# Battery_Block.net
KiCad netlist of a schematic drawn in EAGLE
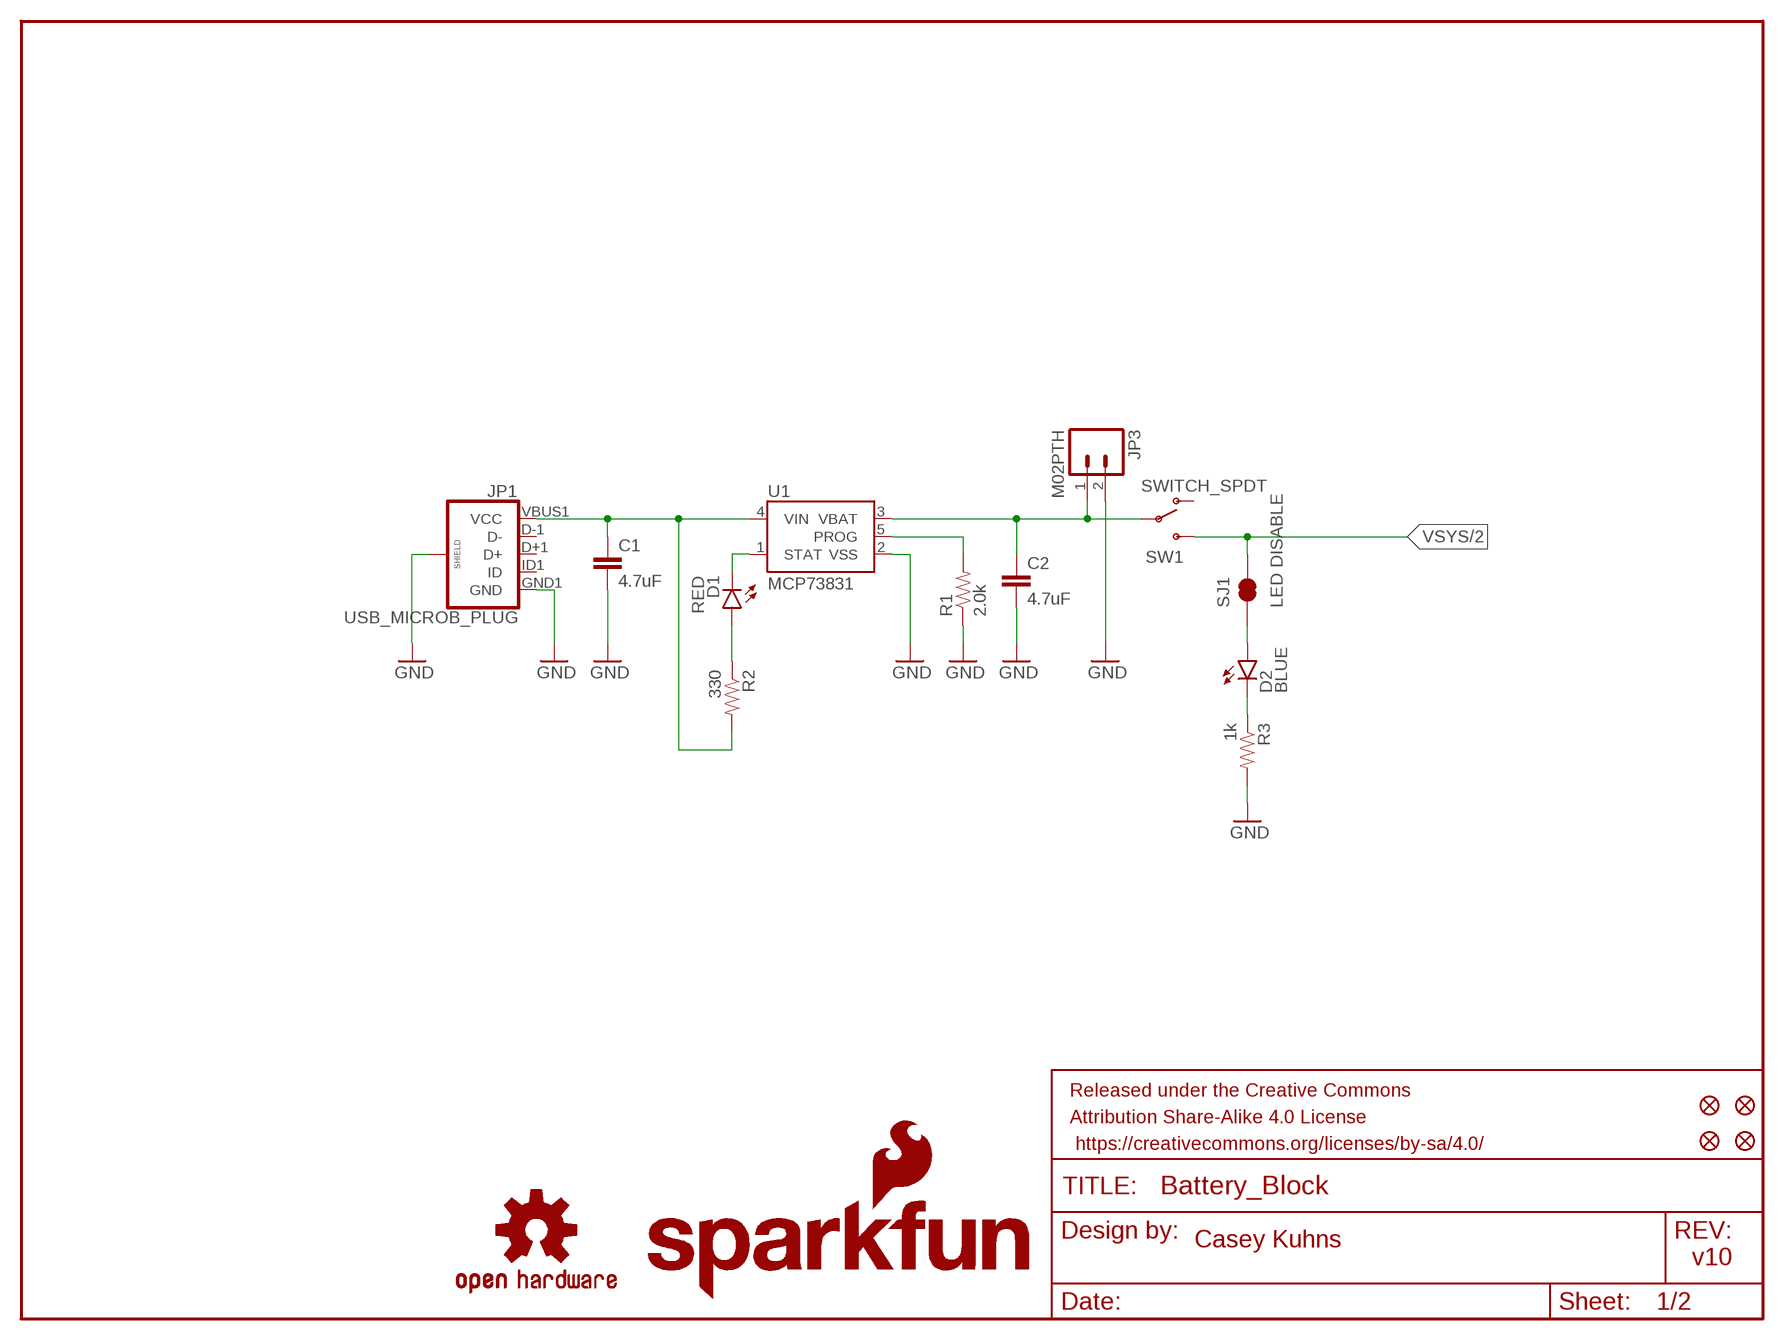
[diagram p0: schematic, sheet 1]
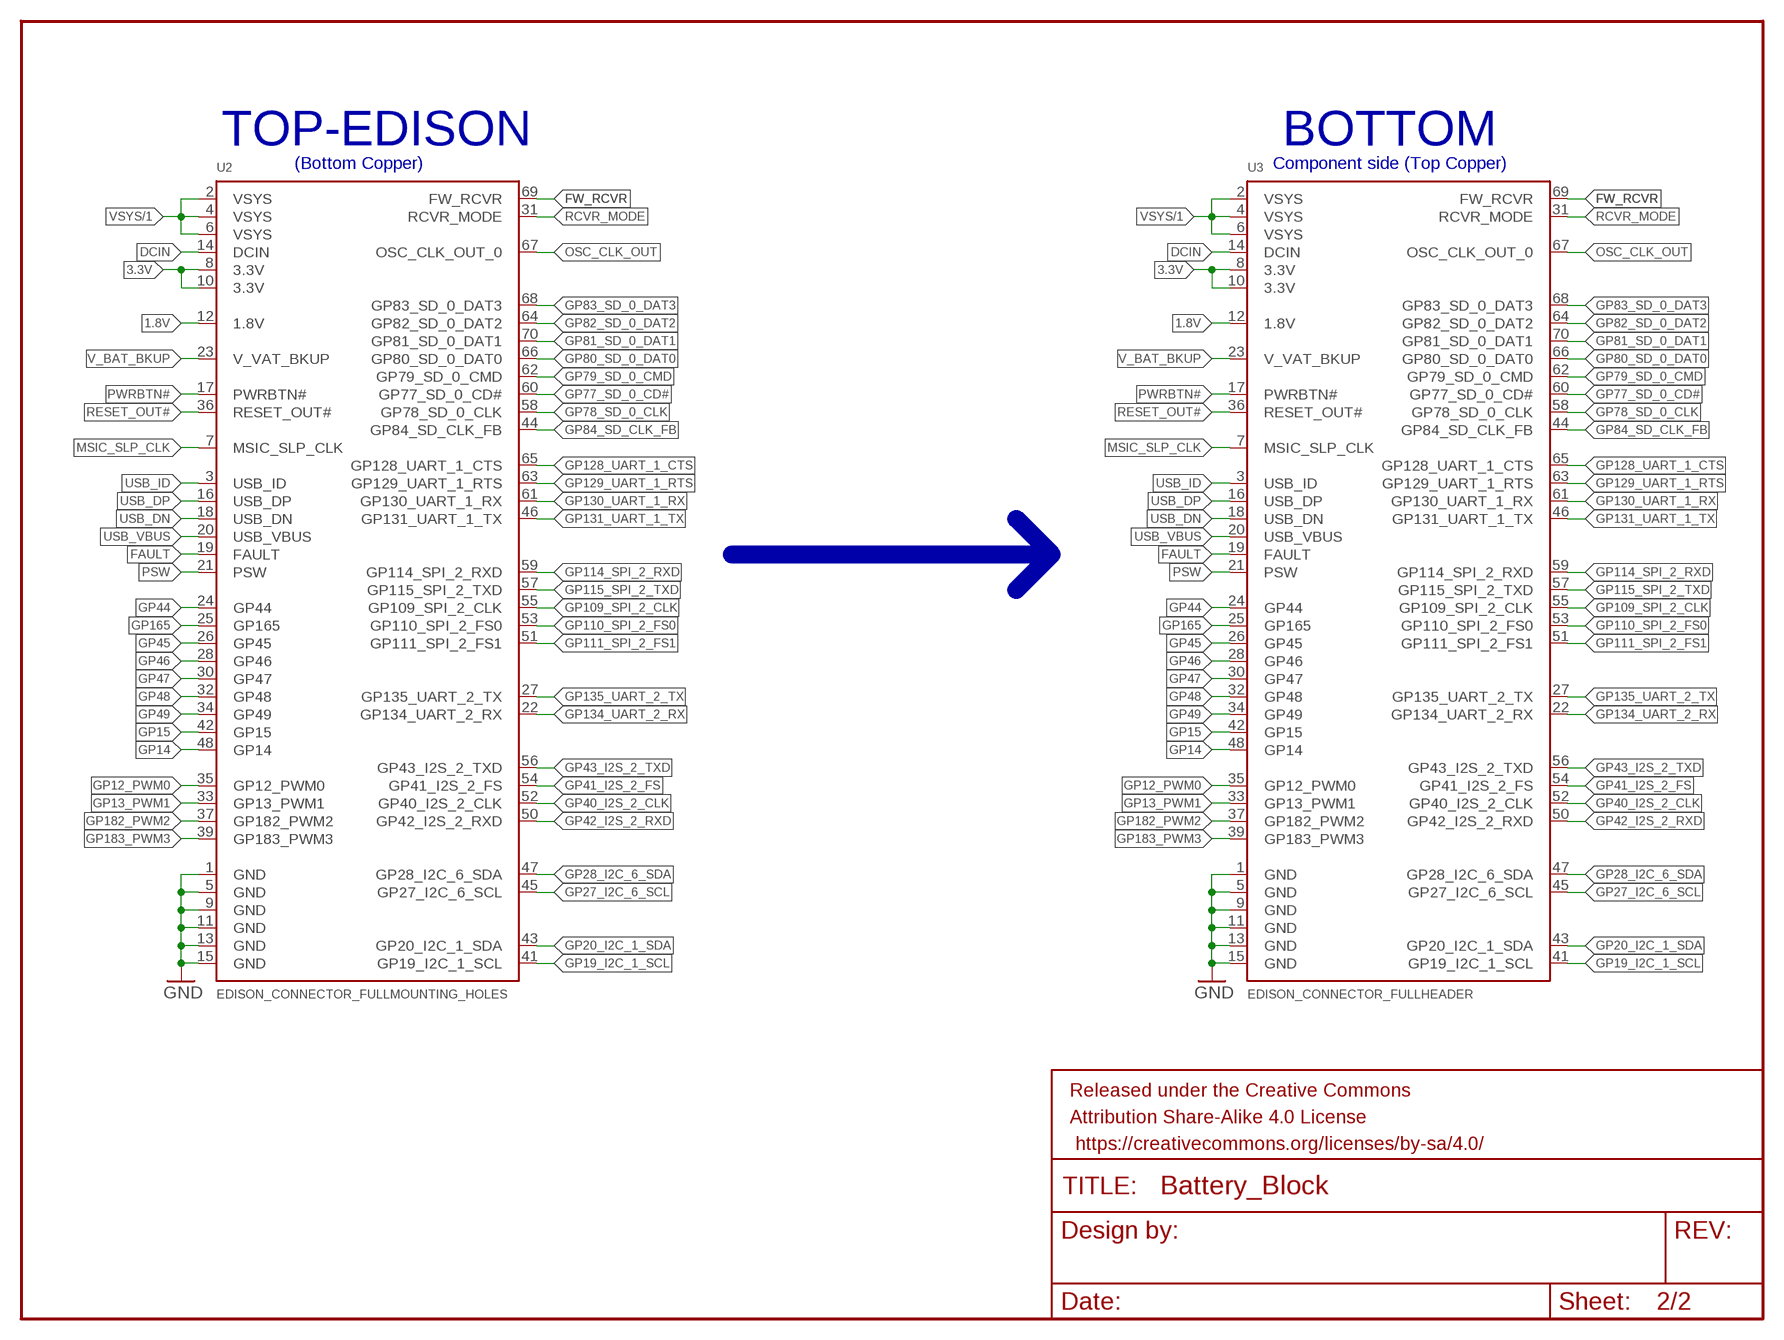
[diagram p1: schematic, sheet 2]

(export (version "E")
  (design (tool "Eeschema 10.0.6"))
  (components
    (comp (ref "FRAME2")
      (value "FRAME-LETTER")
      (footprint "eagle-import:CREATIVE_COMMONS")
      (libsource (lib "eagle-import") (part "FRAME-LETTER"))
    )
    (comp (ref "U2")
      (value "EDISON_CONNECTOR_FULLMOUNTING_HOLES")
      (footprint "eagle-import:EDISON_DAUGHTER")
      (libsource (lib "eagle-import") (part "EDISON_CONNECTOR_FULLMOUNTING_HOLES"))
    )
    (comp (ref "U3")
      (value "EDISON_CONNECTOR_FULLHEADER")
      (footprint "eagle-import:DF40C-70DP-0.4(51)")
      (libsource (lib "eagle-import") (part "EDISON_CONNECTOR_FULLHEADER"))
    )
    (comp (ref "C1")
      (value "4.7uF")
      (footprint "eagle-import:0603-CAP")
      (libsource (lib "eagle-import") (part "4.7UF-6.3V-10%(0603)0603"))
    )
    (comp (ref "C2")
      (value "4.7uF")
      (footprint "eagle-import:0603-CAP")
      (libsource (lib "eagle-import") (part "4.7UF-6.3V-10%(0603)0603"))
    )
    (comp (ref "D1")
      (value "RED")
      (footprint "eagle-import:LED-0603")
      (libsource (lib "eagle-import") (part "LED-RED0603"))
    )
    (comp (ref "D2")
      (value "BLUE")
      (footprint "eagle-import:LED-0603")
      (libsource (lib "eagle-import") (part "LED-BLUE0603"))
    )
    (comp (ref "FID1")
      (value "FIDUCIAL1X2")
      (footprint "eagle-import:FIDUCIAL-1X2")
      (libsource (lib "eagle-import") (part "FIDUCIAL1X2"))
    )
    (comp (ref "FID2")
      (value "FIDUCIAL1X2")
      (footprint "eagle-import:FIDUCIAL-1X2")
      (libsource (lib "eagle-import") (part "FIDUCIAL1X2"))
    )
    (comp (ref "FID3")
      (value "FIDUCIAL1X2")
      (footprint "eagle-import:FIDUCIAL-1X2")
      (libsource (lib "eagle-import") (part "FIDUCIAL1X2"))
    )
    (comp (ref "FID4")
      (value "FIDUCIAL1X2")
      (footprint "eagle-import:FIDUCIAL-1X2")
      (libsource (lib "eagle-import") (part "FIDUCIAL1X2"))
    )
    (comp (ref "FRAME1")
      (value "FRAME-LETTER")
      (footprint "eagle-import:CREATIVE_COMMONS")
      (libsource (lib "eagle-import") (part "FRAME-LETTER"))
    )
    (comp (ref "JP1")
      (value "USB_MICROB_PLUG")
      (footprint "eagle-import:USB-B-MICRO-SMD_V03")
      (libsource (lib "eagle-import") (part "USB_MICROB_PLUGCONN-11752"))
    )
    (comp (ref "JP3")
      (value "M02PTH")
      (footprint "eagle-import:1X02")
      (libsource (lib "eagle-import") (part "M02PTH"))
    )
    (comp (ref "LOGO1")
      (value "OSHW-LOGOS")
      (footprint "eagle-import:OSHW-LOGO-S")
      (libsource (lib "eagle-import") (part "OSHW-LOGOS"))
    )
    (comp (ref "LOGO4")
      (value "SFE_LOGO_NAME_FLAME.1_INCH")
      (footprint "eagle-import:SFE_LOGO_NAME_FLAME_.1")
      (libsource (lib "eagle-import") (part "SFE_LOGO_NAME_FLAME.1_INCH"))
    )
    (comp (ref "R1")
      (value "2.0k")
      (footprint "eagle-import:0603-RES")
      (libsource (lib "eagle-import") (part "2.0KOHM1/10W5%(0603)"))
    )
    (comp (ref "R2")
      (value "330")
      (footprint "eagle-import:0603-RES")
      (libsource (lib "eagle-import") (part "330OHM1/10W1%(0603)"))
    )
    (comp (ref "R3")
      (value "1k")
      (footprint "eagle-import:0603-RES")
      (libsource (lib "eagle-import") (part "1KOHM1/10W1%(0603)"))
    )
    (comp (ref "SJ1")
      (value "LED DISABLE")
      (footprint "eagle-import:PAD-JUMPER-2-NC_BY_TRACE_YES_SILK")
      (libsource (lib "eagle-import") (part "JUMPER-PAD-2-NC_BY_TRACE"))
    )
    (comp (ref "SW1")
      (value "SWITCH_SPDT")
      (footprint "eagle-import:KPS-1290")
      (libsource (lib "eagle-import") (part "SWITCH_SPDT"))
    )
    (comp (ref "U1")
      (value "MCP73831")
      (footprint "eagle-import:SOT23-5")
      (libsource (lib "eagle-import") (part "MCP73831"))
    )
  )
  (nets
    (net (code "1") (name "1.8V") (class "Default")
      (node (ref "U2") (pin "12") (pinfunction "1.8V_12") (pintype "bidirectional"))
      (node (ref "U3") (pin "12") (pinfunction "1.8V_12") (pintype "bidirectional"))
    )
    (net (code "2") (name "3.3V") (class "Default")
      (node (ref "U2") (pin "10") (pinfunction "3.3V_10") (pintype "bidirectional"))
      (node (ref "U2") (pin "8") (pinfunction "3.3V_8") (pintype "bidirectional"))
      (node (ref "U3") (pin "10") (pinfunction "3.3V_10") (pintype "bidirectional"))
      (node (ref "U3") (pin "8") (pinfunction "3.3V_8") (pintype "bidirectional"))
    )
    (net (code "3") (name "DCIN") (class "Default")
      (node (ref "U2") (pin "14") (pinfunction "DCIN_14") (pintype "bidirectional"))
      (node (ref "U3") (pin "14") (pinfunction "DCIN_14") (pintype "bidirectional"))
    )
    (net (code "4") (name "FAULT") (class "Default")
      (node (ref "U2") (pin "19") (pinfunction "FAULT_19") (pintype "bidirectional"))
      (node (ref "U3") (pin "19") (pinfunction "FAULT_19") (pintype "bidirectional"))
    )
    (net (code "5") (name "FW_RCVR") (class "Default")
      (node (ref "U2") (pin "69") (pinfunction "FW_RCVR_69") (pintype "bidirectional"))
      (node (ref "U3") (pin "69") (pinfunction "FW_RCVR_69") (pintype "bidirectional"))
    )
    (net (code "6") (name "GND") (class "Default")
      (node (ref "C1") (pin "2") (pinfunction "2_2") (pintype "passive"))
      (node (ref "C2") (pin "2") (pinfunction "2_2") (pintype "passive"))
      (node (ref "JP1") (pin "GND1") (pinfunction "GND_GND1") (pintype "bidirectional"))
      (node (ref "JP1") (pin "SHIELD1") (pinfunction "SHIELD_SHIELD1") (pintype "bidirectional"))
      (node (ref "JP1") (pin "SHIELD2") (pinfunction "SHIELD_SHIELD2") (pintype "bidirectional"))
      (node (ref "JP1") (pin "SHIELD3") (pinfunction "SHIELD_SHIELD3") (pintype "bidirectional"))
      (node (ref "JP3") (pin "2") (pinfunction "2_2") (pintype "passive"))
      (node (ref "R1") (pin "1") (pinfunction "1_1") (pintype "passive"))
      (node (ref "R3") (pin "2") (pinfunction "2_2") (pintype "passive"))
      (node (ref "U1") (pin "2") (pinfunction "VSS_2") (pintype "power_in"))
      (node (ref "U2") (pin "1") (pinfunction "GND_1") (pintype "bidirectional"))
      (node (ref "U2") (pin "11") (pinfunction "GND_11") (pintype "bidirectional"))
      (node (ref "U2") (pin "13") (pinfunction "GND_13") (pintype "bidirectional"))
      (node (ref "U2") (pin "15") (pinfunction "GND_15") (pintype "bidirectional"))
      (node (ref "U2") (pin "5") (pinfunction "GND_5") (pintype "bidirectional"))
      (node (ref "U2") (pin "9") (pinfunction "GND_9") (pintype "bidirectional"))
      (node (ref "U3") (pin "1") (pinfunction "GND_1") (pintype "bidirectional"))
      (node (ref "U3") (pin "11") (pinfunction "GND_11") (pintype "bidirectional"))
      (node (ref "U3") (pin "13") (pinfunction "GND_13") (pintype "bidirectional"))
      (node (ref "U3") (pin "15") (pinfunction "GND_15") (pintype "bidirectional"))
      (node (ref "U3") (pin "5") (pinfunction "GND_5") (pintype "bidirectional"))
      (node (ref "U3") (pin "9") (pinfunction "GND_9") (pintype "bidirectional"))
    )
    (net (code "7") (name "GP12_PWM0") (class "Default")
      (node (ref "U2") (pin "35") (pinfunction "GP12_PWM0_35") (pintype "bidirectional"))
      (node (ref "U3") (pin "35") (pinfunction "GP12_PWM0_35") (pintype "bidirectional"))
    )
    (net (code "8") (name "GP13_PWM1") (class "Default")
      (node (ref "U2") (pin "33") (pinfunction "GP13_PWM1_33") (pintype "bidirectional"))
      (node (ref "U3") (pin "33") (pinfunction "GP13_PWM1_33") (pintype "bidirectional"))
    )
    (net (code "9") (name "GP14") (class "Default")
      (node (ref "U2") (pin "48") (pinfunction "GP14_48") (pintype "bidirectional"))
      (node (ref "U3") (pin "48") (pinfunction "GP14_48") (pintype "bidirectional"))
    )
    (net (code "10") (name "GP15") (class "Default")
      (node (ref "U2") (pin "42") (pinfunction "GP15_42") (pintype "bidirectional"))
      (node (ref "U3") (pin "42") (pinfunction "GP15_42") (pintype "bidirectional"))
    )
    (net (code "11") (name "GP19_I2C_1_SCL") (class "Default")
      (node (ref "U2") (pin "41") (pinfunction "GP19_I2C_1_SCL_41") (pintype "bidirectional"))
      (node (ref "U3") (pin "41") (pinfunction "GP19_I2C_1_SCL_41") (pintype "bidirectional"))
    )
    (net (code "12") (name "GP20_I2C_1_SDA") (class "Default")
      (node (ref "U2") (pin "43") (pinfunction "GP20_I2C_1_SDA_43") (pintype "bidirectional"))
      (node (ref "U3") (pin "43") (pinfunction "GP20_I2C_1_SDA_43") (pintype "bidirectional"))
    )
    (net (code "13") (name "GP27_I2C_6_SCL") (class "Default")
      (node (ref "U2") (pin "45") (pinfunction "GP27_I2C_6_SCL_45") (pintype "bidirectional"))
      (node (ref "U3") (pin "45") (pinfunction "GP27_I2C_6_SCL_45") (pintype "bidirectional"))
    )
    (net (code "14") (name "GP28_I2C_6_SDA") (class "Default")
      (node (ref "U2") (pin "47") (pinfunction "GP28_I2C_6_SDA_47") (pintype "bidirectional"))
      (node (ref "U3") (pin "47") (pinfunction "GP28_I2C_6_SDA_47") (pintype "bidirectional"))
    )
    (net (code "15") (name "GP40_I2S_2_CLK") (class "Default")
      (node (ref "U2") (pin "52") (pinfunction "GP40_I2S_2_CLK_52") (pintype "bidirectional"))
      (node (ref "U3") (pin "52") (pinfunction "GP40_I2S_2_CLK_52") (pintype "bidirectional"))
    )
    (net (code "16") (name "GP41_I2S_2_FS") (class "Default")
      (node (ref "U2") (pin "54") (pinfunction "GP41_I2S_2_FS_54") (pintype "bidirectional"))
      (node (ref "U3") (pin "54") (pinfunction "GP41_I2S_2_FS_54") (pintype "bidirectional"))
    )
    (net (code "17") (name "GP42_I2S_2_RXD") (class "Default")
      (node (ref "U2") (pin "50") (pinfunction "GP42_I2S_2_RXD_50") (pintype "bidirectional"))
      (node (ref "U3") (pin "50") (pinfunction "GP42_I2S_2_RXD_50") (pintype "bidirectional"))
    )
    (net (code "18") (name "GP43_I2S_2_TXD") (class "Default")
      (node (ref "U2") (pin "56") (pinfunction "GP43_I2S_2_TXD_56") (pintype "bidirectional"))
      (node (ref "U3") (pin "56") (pinfunction "GP43_I2S_2_TXD_56") (pintype "bidirectional"))
    )
    (net (code "19") (name "GP44") (class "Default")
      (node (ref "U2") (pin "24") (pinfunction "GP44_24") (pintype "bidirectional"))
      (node (ref "U3") (pin "24") (pinfunction "GP44_24") (pintype "bidirectional"))
    )
    (net (code "20") (name "GP45") (class "Default")
      (node (ref "U2") (pin "26") (pinfunction "GP45_26") (pintype "bidirectional"))
      (node (ref "U3") (pin "26") (pinfunction "GP45_26") (pintype "bidirectional"))
    )
    (net (code "21") (name "GP46") (class "Default")
      (node (ref "U2") (pin "28") (pinfunction "GP46_28") (pintype "bidirectional"))
      (node (ref "U3") (pin "28") (pinfunction "GP46_28") (pintype "bidirectional"))
    )
    (net (code "22") (name "GP47") (class "Default")
      (node (ref "U2") (pin "30") (pinfunction "GP47_30") (pintype "bidirectional"))
      (node (ref "U3") (pin "30") (pinfunction "GP47_30") (pintype "bidirectional"))
    )
    (net (code "23") (name "GP48") (class "Default")
      (node (ref "U2") (pin "32") (pinfunction "GP48_32") (pintype "bidirectional"))
      (node (ref "U3") (pin "32") (pinfunction "GP48_32") (pintype "bidirectional"))
    )
    (net (code "24") (name "GP49") (class "Default")
      (node (ref "U2") (pin "34") (pinfunction "GP49_34") (pintype "bidirectional"))
      (node (ref "U3") (pin "34") (pinfunction "GP49_34") (pintype "bidirectional"))
    )
    (net (code "25") (name "GP77_SD_0_CD#") (class "Default")
      (node (ref "U2") (pin "60") (pinfunction "GP77_SD_0_CD#_60") (pintype "bidirectional"))
      (node (ref "U3") (pin "60") (pinfunction "GP77_SD_0_CD#_60") (pintype "bidirectional"))
    )
    (net (code "26") (name "GP78_SD_0_CLK") (class "Default")
      (node (ref "U2") (pin "58") (pinfunction "GP78_SD_0_CLK_58") (pintype "bidirectional"))
      (node (ref "U3") (pin "58") (pinfunction "GP78_SD_0_CLK_58") (pintype "bidirectional"))
    )
    (net (code "27") (name "GP79_SD_0_CMD") (class "Default")
      (node (ref "U2") (pin "62") (pinfunction "GP79_SD_0_CMD_62") (pintype "bidirectional"))
      (node (ref "U3") (pin "62") (pinfunction "GP79_SD_0_CMD_62") (pintype "bidirectional"))
    )
    (net (code "28") (name "GP80_SD_0_DAT0") (class "Default")
      (node (ref "U2") (pin "66") (pinfunction "GP80_SD_0_DAT0_66") (pintype "bidirectional"))
      (node (ref "U3") (pin "66") (pinfunction "GP80_SD_0_DAT0_66") (pintype "bidirectional"))
    )
    (net (code "29") (name "GP81_SD_0_DAT1") (class "Default")
      (node (ref "U2") (pin "70") (pinfunction "GP81_SD_0_DAT1_70") (pintype "bidirectional"))
      (node (ref "U3") (pin "70") (pinfunction "GP81_SD_0_DAT1_70") (pintype "bidirectional"))
    )
    (net (code "30") (name "GP82_SD_0_DAT2") (class "Default")
      (node (ref "U2") (pin "64") (pinfunction "GP82_SD_0_DAT2_64") (pintype "bidirectional"))
      (node (ref "U3") (pin "64") (pinfunction "GP82_SD_0_DAT2_64") (pintype "bidirectional"))
    )
    (net (code "31") (name "GP83_SD_0_DAT3") (class "Default")
      (node (ref "U2") (pin "68") (pinfunction "GP83_SD_0_DAT3_68") (pintype "bidirectional"))
      (node (ref "U3") (pin "68") (pinfunction "GP83_SD_0_DAT3_68") (pintype "bidirectional"))
    )
    (net (code "32") (name "GP84_SD_CLK_FB") (class "Default")
      (node (ref "U2") (pin "44") (pinfunction "GP84_SD_CLK_FB_44") (pintype "bidirectional"))
      (node (ref "U3") (pin "44") (pinfunction "GP84_SD_CLK_FB_44") (pintype "bidirectional"))
    )
    (net (code "33") (name "GP109_SPI_2_CLK") (class "Default")
      (node (ref "U2") (pin "55") (pinfunction "GP109_SPI_2_CLK_55") (pintype "bidirectional"))
      (node (ref "U3") (pin "55") (pinfunction "GP109_SPI_2_CLK_55") (pintype "bidirectional"))
    )
    (net (code "34") (name "GP110_SPI_2_FS0") (class "Default")
      (node (ref "U2") (pin "53") (pinfunction "GP110_SPI_2_FS0_53") (pintype "bidirectional"))
      (node (ref "U3") (pin "53") (pinfunction "GP110_SPI_2_FS0_53") (pintype "bidirectional"))
    )
    (net (code "35") (name "GP111_SPI_2_FS1") (class "Default")
      (node (ref "U2") (pin "51") (pinfunction "GP111_SPI_2_FS1_51") (pintype "bidirectional"))
      (node (ref "U3") (pin "51") (pinfunction "GP111_SPI_2_FS1_51") (pintype "bidirectional"))
    )
    (net (code "36") (name "GP114_SPI_2_RXD") (class "Default")
      (node (ref "U2") (pin "59") (pinfunction "GP114_SPI_2_RXD_59") (pintype "bidirectional"))
      (node (ref "U3") (pin "59") (pinfunction "GP114_SPI_2_RXD_59") (pintype "bidirectional"))
    )
    (net (code "37") (name "GP115_SPI_2_TXD") (class "Default")
      (node (ref "U2") (pin "57") (pinfunction "GP115_SPI_2_TXD_57") (pintype "bidirectional"))
      (node (ref "U3") (pin "57") (pinfunction "GP115_SPI_2_TXD_57") (pintype "bidirectional"))
    )
    (net (code "38") (name "GP128_UART_1_CTS") (class "Default")
      (node (ref "U2") (pin "65") (pinfunction "GP128_UART_1_CTS_65") (pintype "bidirectional"))
      (node (ref "U3") (pin "65") (pinfunction "GP128_UART_1_CTS_65") (pintype "bidirectional"))
    )
    (net (code "39") (name "GP129_UART_1_RTS") (class "Default")
      (node (ref "U2") (pin "63") (pinfunction "GP129_UART_1_RTS_63") (pintype "bidirectional"))
      (node (ref "U3") (pin "63") (pinfunction "GP129_UART_1_RTS_63") (pintype "bidirectional"))
    )
    (net (code "40") (name "GP130_UART_1_RX") (class "Default")
      (node (ref "U2") (pin "61") (pinfunction "GP130_UART_1_RX_61") (pintype "bidirectional"))
      (node (ref "U3") (pin "61") (pinfunction "GP130_UART_1_RX_61") (pintype "bidirectional"))
    )
    (net (code "41") (name "GP131_UART_1_TX") (class "Default")
      (node (ref "U2") (pin "46") (pinfunction "GP131_UART_1_TX_46") (pintype "bidirectional"))
      (node (ref "U3") (pin "46") (pinfunction "GP131_UART_1_TX_46") (pintype "bidirectional"))
    )
    (net (code "42") (name "GP134_UART_2_RX") (class "Default")
      (node (ref "U2") (pin "22") (pinfunction "GP134_UART_2_RX_22") (pintype "bidirectional"))
      (node (ref "U3") (pin "22") (pinfunction "GP134_UART_2_RX_22") (pintype "bidirectional"))
    )
    (net (code "43") (name "GP135_UART_2_TX") (class "Default")
      (node (ref "U2") (pin "27") (pinfunction "GP135_UART_2_TX_27") (pintype "bidirectional"))
      (node (ref "U3") (pin "27") (pinfunction "GP135_UART_2_TX_27") (pintype "bidirectional"))
    )
    (net (code "44") (name "GP165") (class "Default")
      (node (ref "U2") (pin "25") (pinfunction "GP165_25") (pintype "bidirectional"))
      (node (ref "U3") (pin "25") (pinfunction "GP165_25") (pintype "bidirectional"))
    )
    (net (code "45") (name "GP182_PWM2") (class "Default")
      (node (ref "U2") (pin "37") (pinfunction "GP182_PWM2_37") (pintype "bidirectional"))
      (node (ref "U3") (pin "37") (pinfunction "GP182_PWM2_37") (pintype "bidirectional"))
    )
    (net (code "46") (name "GP183_PWM3") (class "Default")
      (node (ref "U2") (pin "39") (pinfunction "GP183_PWM3_39") (pintype "bidirectional"))
      (node (ref "U3") (pin "39") (pinfunction "GP183_PWM3_39") (pintype "bidirectional"))
    )
    (net (code "47") (name "MSIC_SLP_CLK") (class "Default")
      (node (ref "U2") (pin "7") (pinfunction "MSIC_SLP_CLK_7") (pintype "bidirectional"))
      (node (ref "U3") (pin "7") (pinfunction "MSIC_SLP_CLK_7") (pintype "bidirectional"))
    )
    (net (code "48") (name "Net-(D1-PadA)") (class "Default")
      (node (ref "D1") (pin "A") (pinfunction "A_A") (pintype "passive"))
      (node (ref "R2") (pin "1") (pinfunction "1_1") (pintype "passive"))
    )
    (net (code "49") (name "Net-(D2-PadA)") (class "Default")
      (node (ref "D2") (pin "A") (pinfunction "A_A") (pintype "passive"))
      (node (ref "SJ1") (pin "1") (pinfunction "1_1") (pintype "passive"))
    )
    (net (code "50") (name "Net-(D2-PadC)") (class "Default")
      (node (ref "D2") (pin "C") (pinfunction "C_C") (pintype "passive"))
      (node (ref "R3") (pin "1") (pinfunction "1_1") (pintype "passive"))
    )
    (net (code "51") (name "Net-(JP1-VCC)") (class "Default")
      (node (ref "C1") (pin "1") (pinfunction "1_1") (pintype "passive"))
      (node (ref "JP1") (pin "VBUS1") (pinfunction "VCC_VBUS1") (pintype "bidirectional"))
      (node (ref "R2") (pin "2") (pinfunction "2_2") (pintype "passive"))
      (node (ref "U1") (pin "4") (pinfunction "VIN_4") (pintype "power_in"))
    )
    (net (code "52") (name "Net-(U1-PROG)") (class "Default")
      (node (ref "R1") (pin "2") (pinfunction "2_2") (pintype "passive"))
      (node (ref "U1") (pin "5") (pinfunction "PROG_5") (pintype "input"))
    )
    (net (code "53") (name "Net-(U1-STAT)") (class "Default")
      (node (ref "D1") (pin "C") (pinfunction "C_C") (pintype "passive"))
      (node (ref "U1") (pin "1") (pinfunction "STAT_1") (pintype "output"))
    )
    (net (code "54") (name "Net-(U1-VBAT)") (class "Default")
      (node (ref "C2") (pin "1") (pinfunction "1_1") (pintype "passive"))
      (node (ref "JP3") (pin "1") (pinfunction "1_1") (pintype "passive"))
      (node (ref "SW1") (pin "P") (pinfunction "P_P") (pintype "passive"))
      (node (ref "U1") (pin "3") (pinfunction "VBAT_3") (pintype "power_in"))
    )
    (net (code "55") (name "OSC_CLK_OUT") (class "Default")
      (node (ref "U2") (pin "67") (pinfunction "OSC_CLK_OUT_0_67") (pintype "bidirectional"))
      (node (ref "U3") (pin "67") (pinfunction "OSC_CLK_OUT_0_67") (pintype "bidirectional"))
    )
    (net (code "56") (name "PSW") (class "Default")
      (node (ref "U2") (pin "21") (pinfunction "PSW_21") (pintype "bidirectional"))
      (node (ref "U3") (pin "21") (pinfunction "PSW_21") (pintype "bidirectional"))
    )
    (net (code "57") (name "PWRBTN#") (class "Default")
      (node (ref "U2") (pin "17") (pinfunction "PWRBTN#_17") (pintype "bidirectional"))
      (node (ref "U3") (pin "17") (pinfunction "PWRBTN#_17") (pintype "bidirectional"))
    )
    (net (code "58") (name "RCVR_MODE") (class "Default")
      (node (ref "U2") (pin "31") (pinfunction "RCVR_MODE_31") (pintype "bidirectional"))
      (node (ref "U3") (pin "31") (pinfunction "RCVR_MODE_31") (pintype "bidirectional"))
    )
    (net (code "59") (name "RESET_OUT#") (class "Default")
      (node (ref "U2") (pin "36") (pinfunction "RESET_OUT#_36") (pintype "bidirectional"))
      (node (ref "U3") (pin "36") (pinfunction "RESET_OUT#_36") (pintype "bidirectional"))
    )
    (net (code "60") (name "USB_DN") (class "Default")
      (node (ref "U2") (pin "18") (pinfunction "USB_DN_18") (pintype "bidirectional"))
      (node (ref "U3") (pin "18") (pinfunction "USB_DN_18") (pintype "bidirectional"))
    )
    (net (code "61") (name "USB_DP") (class "Default")
      (node (ref "U2") (pin "16") (pinfunction "USB_DP_16") (pintype "bidirectional"))
      (node (ref "U3") (pin "16") (pinfunction "USB_DP_16") (pintype "bidirectional"))
    )
    (net (code "62") (name "USB_ID") (class "Default")
      (node (ref "U2") (pin "3") (pinfunction "USB_ID_3") (pintype "bidirectional"))
      (node (ref "U3") (pin "3") (pinfunction "USB_ID_3") (pintype "bidirectional"))
    )
    (net (code "63") (name "USB_VBUS") (class "Default")
      (node (ref "U2") (pin "20") (pinfunction "USB_VBUS_20") (pintype "bidirectional"))
      (node (ref "U3") (pin "20") (pinfunction "USB_VBUS_20") (pintype "bidirectional"))
    )
    (net (code "64") (name "VSYS") (class "Default")
      (node (ref "SJ1") (pin "2") (pinfunction "2_2") (pintype "passive"))
      (node (ref "SW1") (pin "S") (pinfunction "S_S") (pintype "passive"))
      (node (ref "U2") (pin "2") (pinfunction "VSYS_2") (pintype "bidirectional"))
      (node (ref "U2") (pin "4") (pinfunction "VSYS_4") (pintype "bidirectional"))
      (node (ref "U2") (pin "6") (pinfunction "VSYS_6") (pintype "bidirectional"))
      (node (ref "U3") (pin "2") (pinfunction "VSYS_2") (pintype "bidirectional"))
      (node (ref "U3") (pin "4") (pinfunction "VSYS_4") (pintype "bidirectional"))
      (node (ref "U3") (pin "6") (pinfunction "VSYS_6") (pintype "bidirectional"))
    )
    (net (code "65") (name "V_BAT_BKUP") (class "Default")
      (node (ref "U2") (pin "23") (pinfunction "V_VAT_BKUP_23") (pintype "bidirectional"))
      (node (ref "U3") (pin "23") (pinfunction "V_VAT_BKUP_23") (pintype "bidirectional"))
    )
    (net (code "66") (name "unconnected-(JP1-D+-PadD+1)") (class "Default")
      (node (ref "JP1") (pin "D+1") (pinfunction "D+_D+1") (pintype "bidirectional"))
    )
    (net (code "67") (name "unconnected-(JP1-D--PadD-1)") (class "Default")
      (node (ref "JP1") (pin "D-1") (pinfunction "D-_D-1") (pintype "bidirectional"))
    )
    (net (code "68") (name "unconnected-(JP1-ID-PadID1)") (class "Default")
      (node (ref "JP1") (pin "ID1") (pinfunction "ID_ID1") (pintype "bidirectional"))
    )
    (net (code "69") (name "unconnected-(SW1-PadO)") (class "Default")
      (node (ref "SW1") (pin "O") (pinfunction "O_O") (pintype "passive"))
    )
  )
)
